# Transceiver.net
KiCad netlist of a schematic drawn in Altium Designer
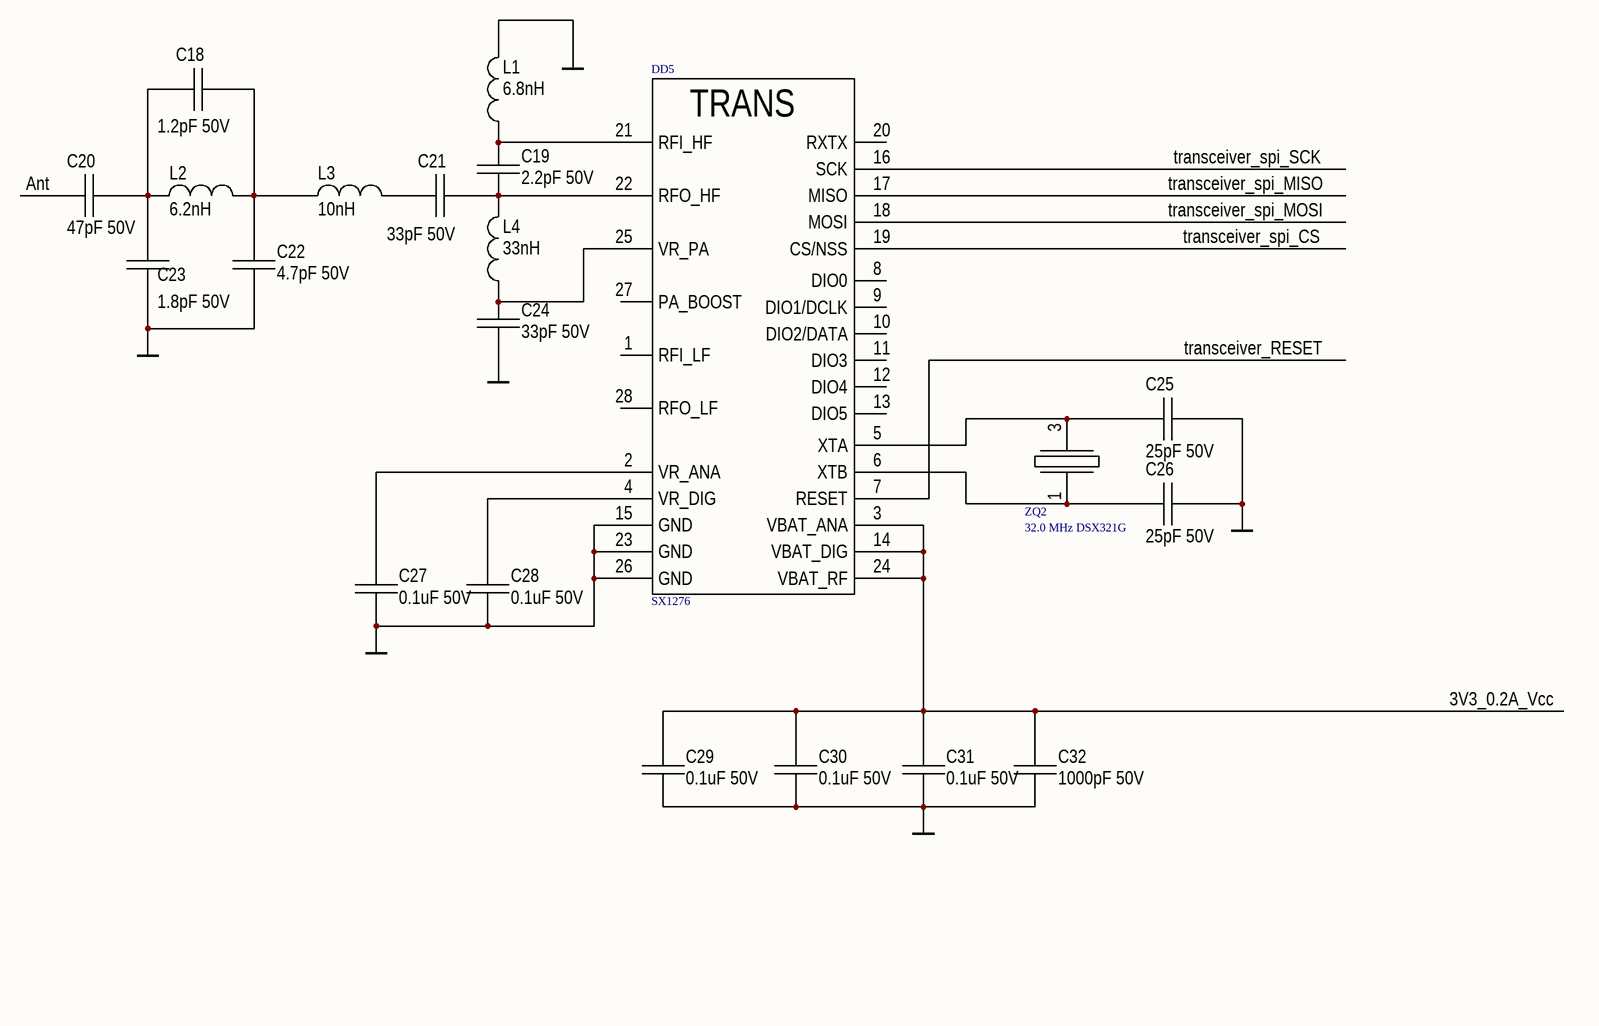
[diagram p0: Transceiver.SchDoc]

(export (version "E")
  (design (tool "Eeschema 10.0.6"))
  (components
    (comp (ref "C18") (value "1.2pF 50V") (footprint "0603_CAP") (libsource (lib "") (part "Cap_np_1")))
    (comp (ref "C19")
      (value "2.2pF 50V")
      (footprint "0603_CAP")
      (libsource (lib "Integrated_Library_tikhovikt") (part "Cap_np"))
    )
    (comp (ref "C20")
      (value "47pF 50V")
      (footprint "0603_CAP")
      (libsource (lib "Integrated_Library_tikhovikt") (part "Cap_np"))
    )
    (comp (ref "C21")
      (value "33pF 50V")
      (footprint "0603_CAP")
      (libsource (lib "Integrated_Library_tikhovikt") (part "Cap_np"))
    )
    (comp (ref "C22")
      (value "4.7pF 50V")
      (footprint "0603_CAP")
      (libsource (lib "Integrated_Library_tikhovikt") (part "Cap_np"))
    )
    (comp (ref "C23")
      (value "1.8pF 50V")
      (footprint "0603_CAP")
      (libsource (lib "Integrated_Library_tikhovikt") (part "Cap_np"))
    )
    (comp (ref "C24")
      (value "33pF 50V")
      (footprint "0603_CAP")
      (libsource (lib "Integrated_Library_tikhovikt") (part "Cap_np"))
    )
    (comp (ref "C25")
      (value "25pF 50V")
      (footprint "0805_CAP")
      (libsource (lib "Integrated_Library_tikhovikt") (part "Cap_np"))
    )
    (comp (ref "C26")
      (value "25pF 50V")
      (footprint "0805_CAP")
      (libsource (lib "Integrated_Library_tikhovikt") (part "Cap_np"))
    )
    (comp (ref "C27")
      (value "0.1uF 50V")
      (footprint "0805_CAP")
      (libsource (lib "Integrated_Library_tikhovikt") (part "Cap_np"))
    )
    (comp (ref "C28")
      (value "0.1uF 50V")
      (footprint "0805_CAP")
      (libsource (lib "Integrated_Library_tikhovikt") (part "Cap_np"))
    )
    (comp (ref "C29")
      (value "0.1uF 50V")
      (footprint "0805_CAP")
      (libsource (lib "Integrated_Library_tikhovikt") (part "Cap_np"))
    )
    (comp (ref "C30")
      (value "0.1uF 50V")
      (footprint "0805_CAP")
      (libsource (lib "Integrated_Library_tikhovikt") (part "Cap_np"))
    )
    (comp (ref "C31")
      (value "0.1uF 50V")
      (footprint "0805_CAP")
      (libsource (lib "Integrated_Library_tikhovikt") (part "Cap_np"))
    )
    (comp (ref "C32")
      (value "1000pF 50V")
      (footprint "0805_CAP")
      (libsource (lib "Integrated_Library_tikhovikt") (part "Cap_np"))
    )
    (comp (ref "DD5")
      (value "SX1276")
      (footprint "qfn28")
      (libsource (lib "Integrated_Library_tikhovikt") (part "SX1276"))
    )
    (comp (ref "L1")
      (value "6.8nH")
      (footprint "0603_ind")
      (libsource (lib "Integrated_Library_tikhovikt") (part "Inductor"))
    )
    (comp (ref "L2")
      (value "6.2nH")
      (footprint "0603_ind")
      (libsource (lib "Integrated_Library_tikhovikt") (part "Inductor"))
    )
    (comp (ref "L3")
      (value "10nH")
      (footprint "0603_ind")
      (libsource (lib "Integrated_Library_tikhovikt") (part "Inductor"))
    )
    (comp (ref "L4")
      (value "33nH")
      (footprint "0603_ind")
      (libsource (lib "Integrated_Library_tikhovikt") (part "Inductor"))
    )
    (comp (ref "ZQ2")
      (value "32.0 MHz DSX321G")
      (footprint "gtxo-93")
      (libsource (lib "Integrated_Library_tikhovikt") (part "Cristall"))
    )
  )
  (nets
    (net (code "1") (name "/3V3_0.2A_Vcc") (class "Default")
      (node (ref "C29") (pin "1") (pinfunction "1_1") (pintype "passive"))
      (node (ref "C30") (pin "1") (pinfunction "1_1") (pintype "passive"))
      (node (ref "C31") (pin "1") (pinfunction "1_1") (pintype "passive"))
      (node (ref "C32") (pin "1") (pinfunction "1_1") (pintype "passive"))
      (node (ref "DD5") (pin "14") (pinfunction "VBAT_DIG_14") (pintype "passive"))
      (node (ref "DD5") (pin "24") (pinfunction "VBAT_RF_24") (pintype "passive"))
      (node (ref "DD5") (pin "3") (pinfunction "VBAT_ANA_3") (pintype "passive"))
    )
    (net (code "2") (name "/Ant") (class "Default")
      (node (ref "C20") (pin "2") (pinfunction "2_2") (pintype "passive"))
    )
    (net (code "3") (name "/transceiver_RESET") (class "Default")
      (node (ref "DD5") (pin "7") (pinfunction "RESET_7") (pintype "passive"))
    )
    (net (code "4") (name "/transceiver_spi_CS") (class "Default")
      (node (ref "DD5") (pin "19") (pinfunction "CS/NSS_19") (pintype "passive"))
    )
    (net (code "5") (name "/transceiver_spi_MISO") (class "Default")
      (node (ref "DD5") (pin "17") (pinfunction "MISO_17") (pintype "passive"))
    )
    (net (code "6") (name "/transceiver_spi_MOSI") (class "Default")
      (node (ref "DD5") (pin "18") (pinfunction "MOSI_18") (pintype "passive"))
    )
    (net (code "7") (name "/transceiver_spi_SCK") (class "Default")
      (node (ref "DD5") (pin "16") (pinfunction "SCK_16") (pintype "passive"))
    )
    (net (code "8") (name "GND") (class "Default")
      (node (ref "C22") (pin "2") (pinfunction "2_2") (pintype "passive"))
      (node (ref "C23") (pin "1") (pinfunction "1_1") (pintype "passive"))
      (node (ref "C24") (pin "2") (pinfunction "2_2") (pintype "passive"))
      (node (ref "C25") (pin "2") (pinfunction "2_2") (pintype "passive"))
      (node (ref "C26") (pin "2") (pinfunction "2_2") (pintype "passive"))
      (node (ref "C27") (pin "1") (pinfunction "1_1") (pintype "passive"))
      (node (ref "C28") (pin "2") (pinfunction "2_2") (pintype "passive"))
      (node (ref "C29") (pin "2") (pinfunction "2_2") (pintype "passive"))
      (node (ref "C30") (pin "2") (pinfunction "2_2") (pintype "passive"))
      (node (ref "C31") (pin "2") (pinfunction "2_2") (pintype "passive"))
      (node (ref "C32") (pin "2") (pinfunction "2_2") (pintype "passive"))
      (node (ref "DD5") (pin "15") (pinfunction "GND_15") (pintype "passive"))
      (node (ref "DD5") (pin "23") (pinfunction "GND_23") (pintype "passive"))
      (node (ref "DD5") (pin "26") (pinfunction "GND_26") (pintype "passive"))
      (node (ref "L1") (pin "2") (pinfunction "2_2") (pintype "passive"))
    )
    (net (code "9") (name "Net-(C18-Pad1)") (class "Default")
      (node (ref "C18") (pin "1") (pinfunction "1_1") (pintype "passive"))
      (node (ref "C20") (pin "1") (pinfunction "1_1") (pintype "passive"))
      (node (ref "C23") (pin "2") (pinfunction "2_2") (pintype "passive"))
      (node (ref "L2") (pin "1") (pinfunction "1_1") (pintype "passive"))
    )
    (net (code "10") (name "Net-(C18-Pad2)") (class "Default")
      (node (ref "C18") (pin "2") (pinfunction "2_2") (pintype "passive"))
      (node (ref "C22") (pin "1") (pinfunction "1_1") (pintype "passive"))
      (node (ref "L2") (pin "2") (pinfunction "2_2") (pintype "passive"))
      (node (ref "L3") (pin "1") (pinfunction "1_1") (pintype "passive"))
    )
    (net (code "11") (name "Net-(C21-Pad2)") (class "Default")
      (node (ref "C21") (pin "2") (pinfunction "2_2") (pintype "passive"))
      (node (ref "L3") (pin "2") (pinfunction "2_2") (pintype "passive"))
    )
    (net (code "12") (name "Net-(DD5-RFI_HF)") (class "Default")
      (node (ref "C19") (pin "2") (pinfunction "2_2") (pintype "passive"))
      (node (ref "DD5") (pin "21") (pinfunction "RFI_HF_21") (pintype "passive"))
      (node (ref "L1") (pin "1") (pinfunction "1_1") (pintype "passive"))
    )
    (net (code "13") (name "Net-(DD5-RFO_HF)") (class "Default")
      (node (ref "C19") (pin "1") (pinfunction "1_1") (pintype "passive"))
      (node (ref "C21") (pin "1") (pinfunction "1_1") (pintype "passive"))
      (node (ref "DD5") (pin "22") (pinfunction "RFO_HF_22") (pintype "passive"))
      (node (ref "L4") (pin "2") (pinfunction "2_2") (pintype "passive"))
    )
    (net (code "14") (name "Net-(DD5-VR_ANA)") (class "Default")
      (node (ref "C27") (pin "2") (pinfunction "2_2") (pintype "passive"))
      (node (ref "DD5") (pin "2") (pinfunction "VR_ANA_2") (pintype "passive"))
    )
    (net (code "15") (name "Net-(DD5-VR_DIG)") (class "Default")
      (node (ref "C28") (pin "1") (pinfunction "1_1") (pintype "passive"))
      (node (ref "DD5") (pin "4") (pinfunction "VR_DIG_4") (pintype "passive"))
    )
    (net (code "16") (name "Net-(DD5-VR_PA)") (class "Default")
      (node (ref "C24") (pin "1") (pinfunction "1_1") (pintype "passive"))
      (node (ref "DD5") (pin "25") (pinfunction "VR_PA_25") (pintype "passive"))
      (node (ref "L4") (pin "1") (pinfunction "1_1") (pintype "passive"))
    )
    (net (code "17") (name "Net-(DD5-XTA)") (class "Default")
      (node (ref "C25") (pin "1") (pinfunction "1_1") (pintype "passive"))
      (node (ref "DD5") (pin "5") (pinfunction "XTA_5") (pintype "passive"))
      (node (ref "ZQ2") (pin "3") (pinfunction "3_3") (pintype "passive"))
    )
    (net (code "18") (name "Net-(DD5-XTB)") (class "Default")
      (node (ref "C26") (pin "1") (pinfunction "1_1") (pintype "passive"))
      (node (ref "DD5") (pin "6") (pinfunction "XTB_6") (pintype "passive"))
      (node (ref "ZQ2") (pin "1") (pinfunction "1_1") (pintype "passive"))
    )
    (net (code "19") (name "unconnected-(DD5-DIO0-Pad8)") (class "Default")
      (node (ref "DD5") (pin "8") (pinfunction "DIO0_8") (pintype "passive"))
    )
    (net (code "20") (name "unconnected-(DD5-DIO1{slash}DCLK-Pad9)") (class "Default")
      (node (ref "DD5") (pin "9") (pinfunction "DIO1/DCLK_9") (pintype "passive"))
    )
    (net (code "21") (name "unconnected-(DD5-DIO2{slash}DATA-Pad10)") (class "Default")
      (node (ref "DD5") (pin "10") (pinfunction "DIO2/DATA_10") (pintype "passive"))
    )
    (net (code "22") (name "unconnected-(DD5-DIO3-Pad11)") (class "Default")
      (node (ref "DD5") (pin "11") (pinfunction "DIO3_11") (pintype "passive"))
    )
    (net (code "23") (name "unconnected-(DD5-DIO4-Pad12)") (class "Default")
      (node (ref "DD5") (pin "12") (pinfunction "DIO4_12") (pintype "passive"))
    )
    (net (code "24") (name "unconnected-(DD5-DIO5-Pad13)") (class "Default")
      (node (ref "DD5") (pin "13") (pinfunction "DIO5_13") (pintype "passive"))
    )
    (net (code "25") (name "unconnected-(DD5-PA_BOOST-Pad27)") (class "Default")
      (node (ref "DD5") (pin "27") (pinfunction "PA_BOOST_27") (pintype "passive"))
    )
    (net (code "26") (name "unconnected-(DD5-RFI_LF-Pad1)") (class "Default")
      (node (ref "DD5") (pin "1") (pinfunction "RFI_LF_1") (pintype "passive"))
    )
    (net (code "27") (name "unconnected-(DD5-RFO_LF-Pad28)") (class "Default")
      (node (ref "DD5") (pin "28") (pinfunction "RFO_LF_28") (pintype "passive"))
    )
    (net (code "28") (name "unconnected-(DD5-RXTX-Pad20)") (class "Default")
      (node (ref "DD5") (pin "20") (pinfunction "RXTX_20") (pintype "passive"))
    )
  )
)
